# Logic_Probe.net
KiCad netlist of a schematic drawn in EAGLE
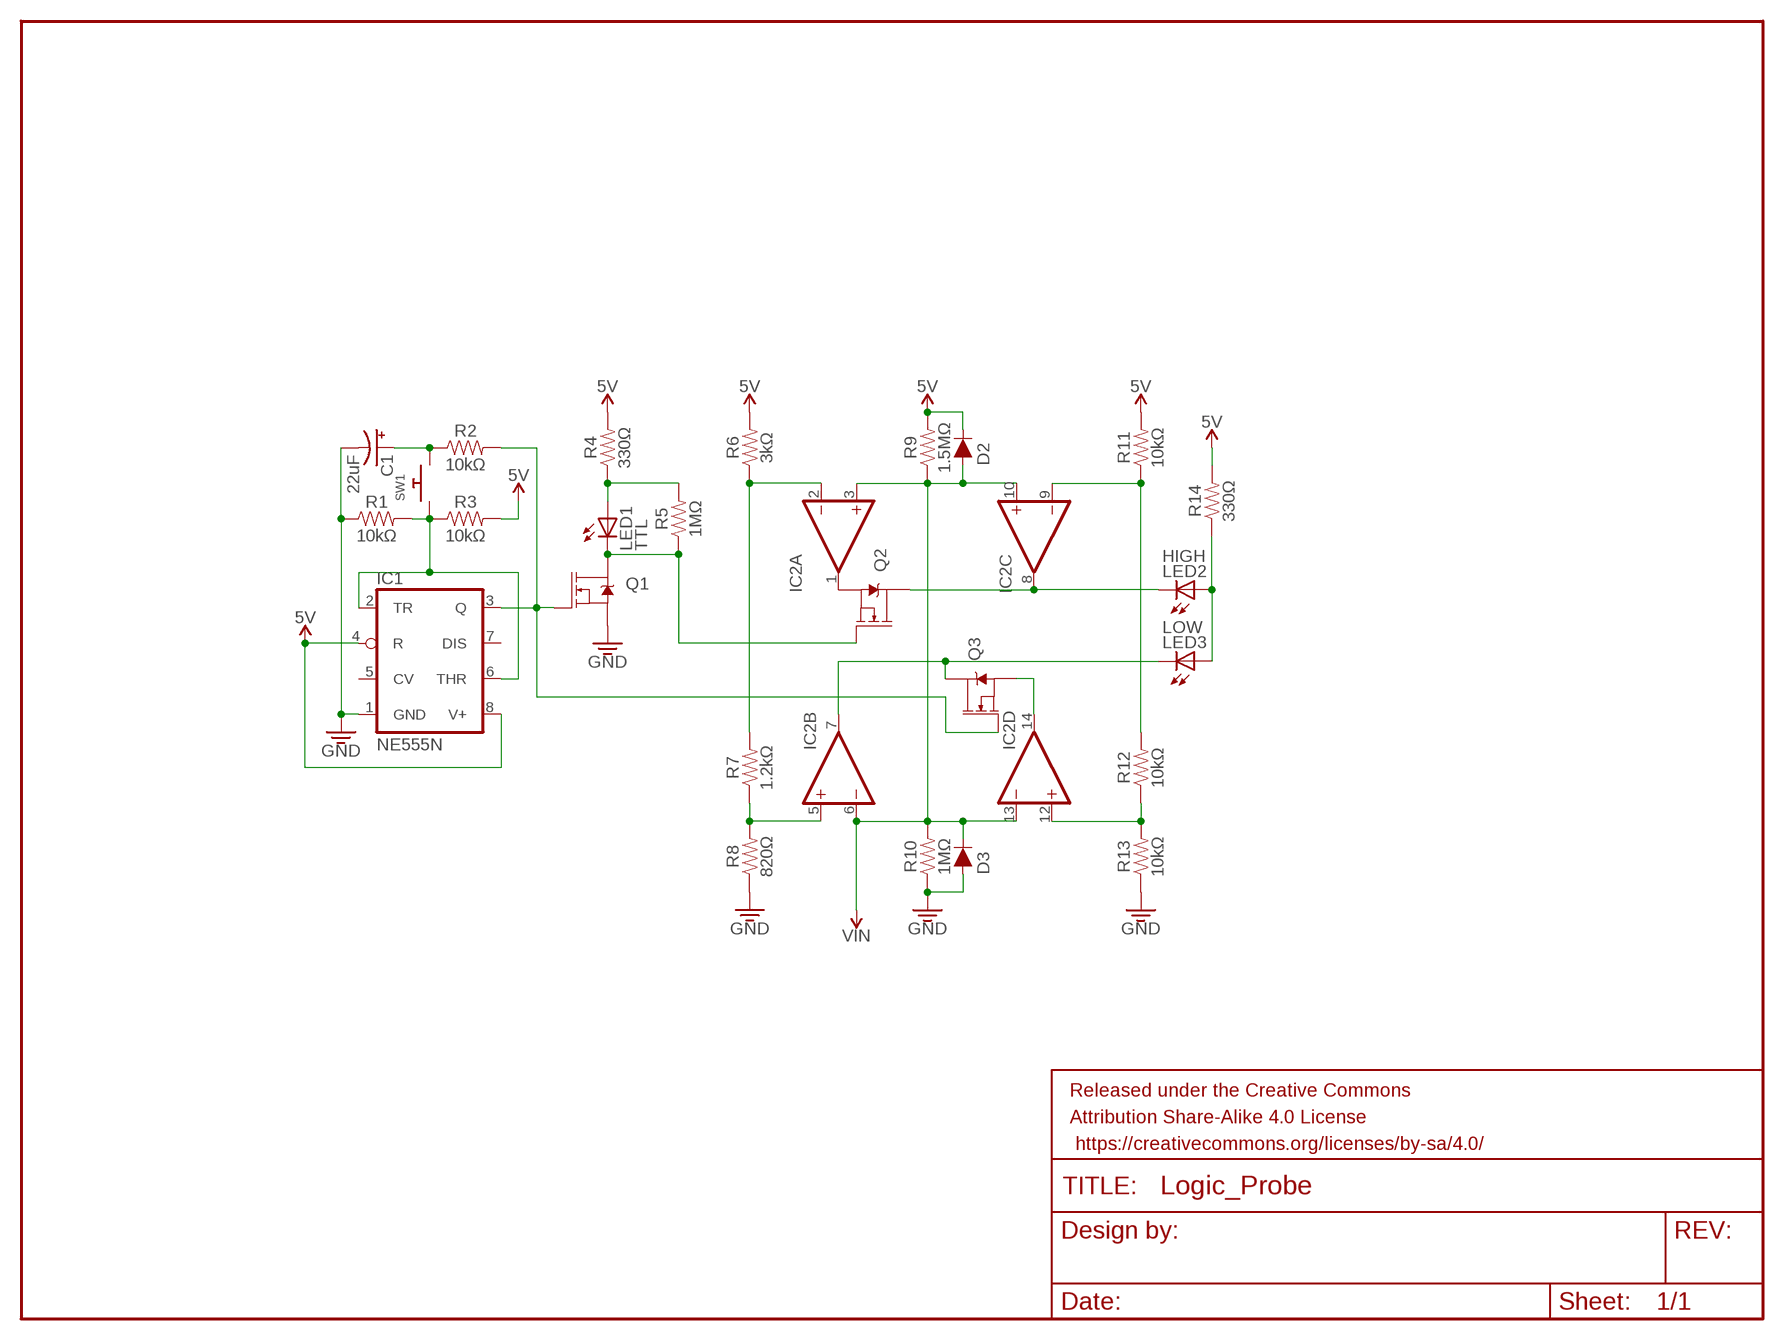
[diagram p0: schematic, sheet 1]

(export (version "E")
  (design (tool "Eeschema 10.0.6"))
  (components
    (comp (ref "C1")
      (value "22uF")
      (footprint "eagle-import:PANASONIC_C")
      (libsource (lib "eagle-import") (part "22UF-POLAR-PANASONIC_C-35V-20%"))
    )
    (comp (ref "D2")
      (value "DIODE-1N4148")
      (footprint "eagle-import:DIODE-1N4148")
      (libsource (lib "eagle-import") (part "DIODE-1N4148"))
    )
    (comp (ref "D3")
      (value "DIODE-1N4148")
      (footprint "eagle-import:DIODE-1N4148")
      (libsource (lib "eagle-import") (part "DIODE-1N4148"))
    )
    (comp (ref "FRAME1")
      (value "FRAME-LETTER")
      (footprint "eagle-import:CREATIVE_COMMONS")
      (libsource (lib "eagle-import") (part "FRAME-LETTER"))
    )
    (comp (ref "IC1")
      (value "NE555N")
      (footprint "eagle-import:DIL08-ROUND")
      (libsource (lib "eagle-import") (part "555NNE"))
    )
    (comp (ref "IC2")
      (value "QUAD_OPAMPP")
      (footprint "eagle-import:DIL14")
      (libsource (lib "eagle-import") (part "QUAD_OPAMPP"))
    )
    (comp (ref "LED1")
      (value "TTL")
      (footprint "eagle-import:LED5MM")
      (libsource (lib "eagle-import") (part "LED5MM"))
    )
    (comp (ref "LED2")
      (value "HIGH")
      (footprint "eagle-import:LED5MM")
      (libsource (lib "eagle-import") (part "LED5MM"))
    )
    (comp (ref "LED3")
      (value "LOW")
      (footprint "eagle-import:LED5MM")
      (libsource (lib "eagle-import") (part "LED5MM"))
    )
    (comp (ref "Q1")
      (value "MOSFET-NCH-2N7002PW")
      (footprint "eagle-import:SOT323")
      (libsource (lib "eagle-import") (part "MOSFET-NCH-2N7002PW"))
    )
    (comp (ref "Q2")
      (value "MOSFET-NCH-2N7002PW")
      (footprint "eagle-import:SOT323")
      (libsource (lib "eagle-import") (part "MOSFET-NCH-2N7002PW"))
    )
    (comp (ref "Q3")
      (value "MOSFET-NCH-2N7002PW")
      (footprint "eagle-import:SOT323")
      (libsource (lib "eagle-import") (part "MOSFET-NCH-2N7002PW"))
    )
    (comp (ref "R1")
      (value "10kΩ")
      (footprint "eagle-import:AXIAL-0.3")
      (libsource (lib "eagle-import") (part "RESISTORAXIAL-0.3"))
    )
    (comp (ref "R2")
      (value "10kΩ")
      (footprint "eagle-import:AXIAL-0.3")
      (libsource (lib "eagle-import") (part "RESISTORAXIAL-0.3"))
    )
    (comp (ref "R3")
      (value "10kΩ")
      (footprint "eagle-import:AXIAL-0.3")
      (libsource (lib "eagle-import") (part "RESISTORAXIAL-0.3"))
    )
    (comp (ref "R4")
      (value "330Ω")
      (footprint "eagle-import:AXIAL-0.3")
      (libsource (lib "eagle-import") (part "RESISTORAXIAL-0.3"))
    )
    (comp (ref "R5")
      (value "1MΩ")
      (footprint "eagle-import:AXIAL-0.3")
      (libsource (lib "eagle-import") (part "RESISTORAXIAL-0.3"))
    )
    (comp (ref "R6")
      (value "3kΩ")
      (footprint "eagle-import:AXIAL-0.3")
      (libsource (lib "eagle-import") (part "RESISTORAXIAL-0.3"))
    )
    (comp (ref "R7")
      (value "1.2kΩ")
      (footprint "eagle-import:AXIAL-0.3")
      (libsource (lib "eagle-import") (part "RESISTORAXIAL-0.3"))
    )
    (comp (ref "R8")
      (value "820Ω")
      (footprint "eagle-import:AXIAL-0.3")
      (libsource (lib "eagle-import") (part "RESISTORAXIAL-0.3"))
    )
    (comp (ref "R9")
      (value "1.5MΩ")
      (footprint "eagle-import:AXIAL-0.3")
      (libsource (lib "eagle-import") (part "RESISTORAXIAL-0.3"))
    )
    (comp (ref "R10")
      (value "1MΩ")
      (footprint "eagle-import:AXIAL-0.3")
      (libsource (lib "eagle-import") (part "RESISTORAXIAL-0.3"))
    )
    (comp (ref "R11")
      (value "10kΩ")
      (footprint "eagle-import:AXIAL-0.3")
      (libsource (lib "eagle-import") (part "RESISTORAXIAL-0.3"))
    )
    (comp (ref "R12")
      (value "10kΩ")
      (footprint "eagle-import:AXIAL-0.3")
      (libsource (lib "eagle-import") (part "RESISTORAXIAL-0.3"))
    )
    (comp (ref "R13")
      (value "10kΩ")
      (footprint "eagle-import:AXIAL-0.3")
      (libsource (lib "eagle-import") (part "RESISTORAXIAL-0.3"))
    )
    (comp (ref "R14")
      (value "330Ω")
      (footprint "eagle-import:AXIAL-0.3")
      (libsource (lib "eagle-import") (part "RESISTORAXIAL-0.3"))
    )
    (comp (ref "SW1")
      (value "SWITCH_PUSHBUTTONEVQ-PE")
      (footprint "eagle-import:TACT_PANA-EVQ")
      (libsource (lib "eagle-import") (part "SWITCH_PUSHBUTTONEVQ-PE"))
    )
  )
  (nets
    (net (code "1") (name "5V") (class "Default")
      (node (ref "D2") (pin "C") (pinfunction "C_C") (pintype "passive"))
      (node (ref "IC1") (pin "4") (pinfunction "R_4") (pintype "input"))
      (node (ref "IC1") (pin "8") (pinfunction "V+_8") (pintype "power_in"))
      (node (ref "R11") (pin "P$2") (pinfunction "2_P$2") (pintype "passive"))
      (node (ref "R14") (pin "P$2") (pinfunction "2_P$2") (pintype "passive"))
      (node (ref "R3") (pin "P$2") (pinfunction "2_P$2") (pintype "passive"))
      (node (ref "R4") (pin "P$2") (pinfunction "2_P$2") (pintype "passive"))
      (node (ref "R6") (pin "P$2") (pinfunction "2_P$2") (pintype "passive"))
      (node (ref "R9") (pin "P$2") (pinfunction "2_P$2") (pintype "passive"))
    )
    (net (code "2") (name "GND") (class "Default")
      (node (ref "C1") (pin "-") (pinfunction "-_-") (pintype "passive"))
      (node (ref "D3") (pin "A") (pinfunction "A_A") (pintype "passive"))
      (node (ref "IC1") (pin "1") (pinfunction "GND_1") (pintype "power_in"))
      (node (ref "Q1") (pin "2") (pinfunction "S_2") (pintype "bidirectional"))
      (node (ref "R1") (pin "P$1") (pinfunction "1_P$1") (pintype "passive"))
      (node (ref "R10") (pin "P$1") (pinfunction "1_P$1") (pintype "passive"))
      (node (ref "R13") (pin "P$1") (pinfunction "1_P$1") (pintype "passive"))
      (node (ref "R8") (pin "P$1") (pinfunction "1_P$1") (pintype "passive"))
    )
    (net (code "3") (name "Net-(IC1-Q)") (class "Default")
      (node (ref "IC1") (pin "3") (pinfunction "Q_3") (pintype "output"))
      (node (ref "Q1") (pin "1") (pinfunction "G_1") (pintype "bidirectional"))
      (node (ref "Q3") (pin "1") (pinfunction "G_1") (pintype "bidirectional"))
      (node (ref "R2") (pin "P$2") (pinfunction "2_P$2") (pintype "passive"))
    )
    (net (code "4") (name "Net-(IC1-THR)") (class "Default")
      (node (ref "IC1") (pin "2") (pinfunction "TR_2") (pintype "input"))
      (node (ref "IC1") (pin "6") (pinfunction "THR_6") (pintype "input"))
      (node (ref "R1") (pin "P$2") (pinfunction "2_P$2") (pintype "passive"))
      (node (ref "R3") (pin "P$1") (pinfunction "1_P$1") (pintype "passive"))
      (node (ref "SW1") (pin "P$1") (pinfunction "P$1_P$1") (pintype "passive"))
    )
    (net (code "5") (name "Net-(IC2A--IN)") (class "Default")
      (node (ref "IC2") (pin "2") (pinfunction "-IN_2") (pintype "input"))
      (node (ref "R6") (pin "P$1") (pinfunction "1_P$1") (pintype "passive"))
      (node (ref "R7") (pin "P$2") (pinfunction "2_P$2") (pintype "passive"))
    )
    (net (code "6") (name "Net-(IC2A-OUT)") (class "Default")
      (node (ref "IC2") (pin "1") (pinfunction "OUT_1") (pintype "output"))
      (node (ref "Q2") (pin "2") (pinfunction "S_2") (pintype "bidirectional"))
    )
    (net (code "7") (name "Net-(IC2B-+IN)") (class "Default")
      (node (ref "IC2") (pin "5") (pinfunction "+IN_5") (pintype "input"))
      (node (ref "R7") (pin "P$1") (pinfunction "1_P$1") (pintype "passive"))
      (node (ref "R8") (pin "P$2") (pinfunction "2_P$2") (pintype "passive"))
    )
    (net (code "8") (name "Net-(IC2B-OUT)") (class "Default")
      (node (ref "IC2") (pin "7") (pinfunction "OUT_7") (pintype "output"))
      (node (ref "LED3") (pin "K") (pinfunction "C_K") (pintype "passive"))
      (node (ref "Q3") (pin "3") (pinfunction "D_3") (pintype "bidirectional"))
    )
    (net (code "9") (name "Net-(IC2C--IN)") (class "Default")
      (node (ref "IC2") (pin "9") (pinfunction "-IN_9") (pintype "input"))
      (node (ref "R11") (pin "P$1") (pinfunction "1_P$1") (pintype "passive"))
      (node (ref "R12") (pin "P$2") (pinfunction "2_P$2") (pintype "passive"))
    )
    (net (code "10") (name "Net-(IC2C-OUT)") (class "Default")
      (node (ref "IC2") (pin "8") (pinfunction "OUT_8") (pintype "output"))
      (node (ref "LED2") (pin "K") (pinfunction "C_K") (pintype "passive"))
      (node (ref "Q2") (pin "3") (pinfunction "D_3") (pintype "bidirectional"))
    )
    (net (code "11") (name "Net-(IC2D-+IN)") (class "Default")
      (node (ref "IC2") (pin "12") (pinfunction "+IN_12") (pintype "input"))
      (node (ref "R12") (pin "P$1") (pinfunction "1_P$1") (pintype "passive"))
      (node (ref "R13") (pin "P$2") (pinfunction "2_P$2") (pintype "passive"))
    )
    (net (code "12") (name "Net-(IC2D-OUT)") (class "Default")
      (node (ref "IC2") (pin "14") (pinfunction "OUT_14") (pintype "output"))
      (node (ref "Q3") (pin "2") (pinfunction "S_2") (pintype "bidirectional"))
    )
    (net (code "13") (name "Net-(LED1-C)") (class "Default")
      (node (ref "LED1") (pin "K") (pinfunction "C_K") (pintype "passive"))
      (node (ref "Q1") (pin "3") (pinfunction "D_3") (pintype "bidirectional"))
      (node (ref "Q2") (pin "1") (pinfunction "G_1") (pintype "bidirectional"))
      (node (ref "R5") (pin "P$1") (pinfunction "1_P$1") (pintype "passive"))
    )
    (net (code "14") (name "Net-(R2-1)") (class "Default")
      (node (ref "C1") (pin "+") (pinfunction "+_+") (pintype "passive"))
      (node (ref "R2") (pin "P$1") (pinfunction "1_P$1") (pintype "passive"))
      (node (ref "SW1") (pin "P$2") (pinfunction "P$2_P$2") (pintype "passive"))
    )
    (net (code "15") (name "Net-(R4-1)") (class "Default")
      (node (ref "LED1") (pin "A") (pinfunction "A_A") (pintype "passive"))
      (node (ref "R4") (pin "P$1") (pinfunction "1_P$1") (pintype "passive"))
      (node (ref "R5") (pin "P$2") (pinfunction "2_P$2") (pintype "passive"))
    )
    (net (code "16") (name "Net-(R14-1)") (class "Default")
      (node (ref "LED2") (pin "A") (pinfunction "A_A") (pintype "passive"))
      (node (ref "LED3") (pin "A") (pinfunction "A_A") (pintype "passive"))
      (node (ref "R14") (pin "P$1") (pinfunction "1_P$1") (pintype "passive"))
    )
    (net (code "17") (name "VIN") (class "Default")
      (node (ref "D2") (pin "A") (pinfunction "A_A") (pintype "passive"))
      (node (ref "D3") (pin "C") (pinfunction "C_C") (pintype "passive"))
      (node (ref "IC2") (pin "10") (pinfunction "+IN_10") (pintype "input"))
      (node (ref "IC2") (pin "13") (pinfunction "-IN_13") (pintype "input"))
      (node (ref "IC2") (pin "3") (pinfunction "+IN_3") (pintype "input"))
      (node (ref "IC2") (pin "6") (pinfunction "-IN_6") (pintype "input"))
      (node (ref "R10") (pin "P$2") (pinfunction "2_P$2") (pintype "passive"))
      (node (ref "R9") (pin "P$1") (pinfunction "1_P$1") (pintype "passive"))
    )
    (net (code "18") (name "unconnected-(IC1-CV-Pad5)") (class "Default")
      (node (ref "IC1") (pin "5") (pinfunction "CV_5") (pintype "input"))
    )
    (net (code "19") (name "unconnected-(IC1-DIS-Pad7)") (class "Default")
      (node (ref "IC1") (pin "7") (pinfunction "DIS_7") (pintype "input"))
    )
  )
)
